# MRCS-Adapter-RJ11.net
KiCad netlist of a schematic drawn in EAGLE
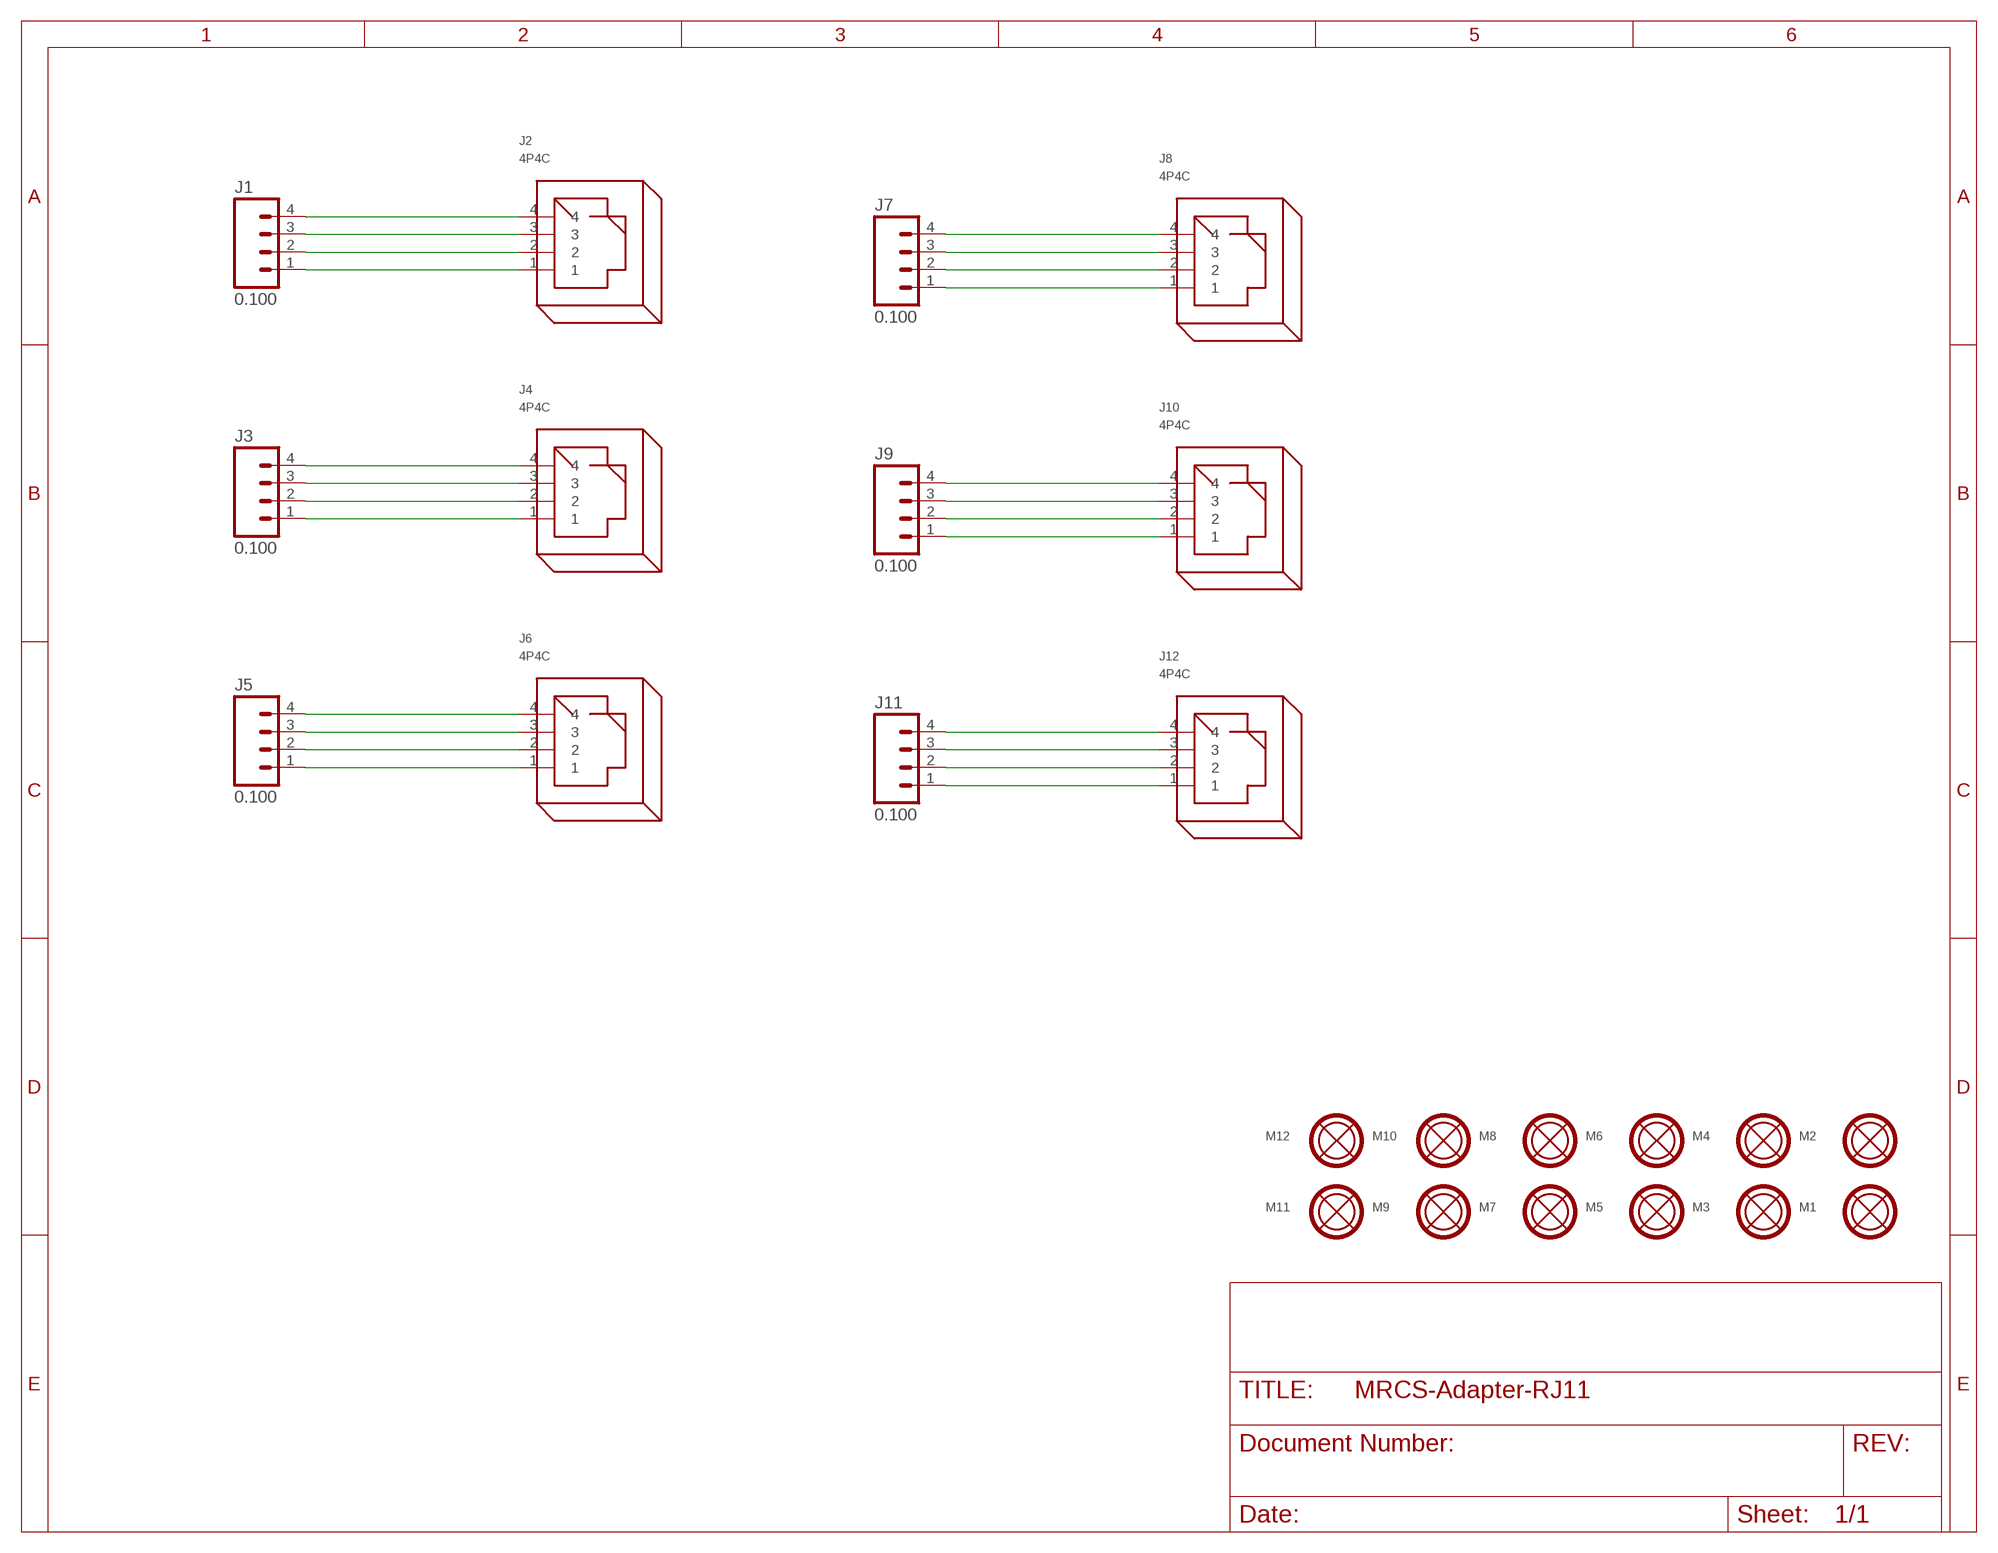
[diagram p0: schematic, sheet 1]

(export (version "E")
  (design (tool "Eeschema 10.0.6"))
  (components
    (comp (ref "J1")
      (value "0.100")
      (footprint "eagle-import:1X04_LOCK")
      (libsource (lib "eagle-import") (part "CONNECTOR-M04LOCK"))
    )
    (comp (ref "J2")
      (value "4P4C")
      (footprint "eagle-import:RJ11")
      (libsource (lib "eagle-import") (part "RJ11"))
    )
    (comp (ref "J3")
      (value "0.100")
      (footprint "eagle-import:1X04_LOCK")
      (libsource (lib "eagle-import") (part "CONNECTOR-M04LOCK"))
    )
    (comp (ref "J4")
      (value "4P4C")
      (footprint "eagle-import:RJ11")
      (libsource (lib "eagle-import") (part "RJ11"))
    )
    (comp (ref "J5")
      (value "0.100")
      (footprint "eagle-import:1X04_LOCK")
      (libsource (lib "eagle-import") (part "CONNECTOR-M04LOCK"))
    )
    (comp (ref "J6")
      (value "4P4C")
      (footprint "eagle-import:RJ11")
      (libsource (lib "eagle-import") (part "RJ11"))
    )
    (comp (ref "J7")
      (value "0.100")
      (footprint "eagle-import:1X04_LOCK")
      (libsource (lib "eagle-import") (part "CONNECTOR-M04LOCK"))
    )
    (comp (ref "J8")
      (value "4P4C")
      (footprint "eagle-import:RJ11")
      (libsource (lib "eagle-import") (part "RJ11"))
    )
    (comp (ref "J9")
      (value "0.100")
      (footprint "eagle-import:1X04_LOCK")
      (libsource (lib "eagle-import") (part "CONNECTOR-M04LOCK"))
    )
    (comp (ref "J10")
      (value "4P4C")
      (footprint "eagle-import:RJ11")
      (libsource (lib "eagle-import") (part "RJ11"))
    )
    (comp (ref "J11")
      (value "0.100")
      (footprint "eagle-import:1X04_LOCK")
      (libsource (lib "eagle-import") (part "CONNECTOR-M04LOCK"))
    )
    (comp (ref "J12")
      (value "4P4C")
      (footprint "eagle-import:RJ11")
      (libsource (lib "eagle-import") (part "RJ11"))
    )
    (comp (ref "M1")
      (value "MOUNTINGHOLE")
      (footprint "eagle-import:MOUNTINGHOLE")
      (libsource (lib "eagle-import") (part "MOUNTINGHOLE"))
    )
    (comp (ref "M2")
      (value "MOUNTINGHOLE")
      (footprint "eagle-import:MOUNTINGHOLE")
      (libsource (lib "eagle-import") (part "MOUNTINGHOLE"))
    )
    (comp (ref "M3")
      (value "MOUNTINGHOLE")
      (footprint "eagle-import:MOUNTINGHOLE")
      (libsource (lib "eagle-import") (part "MOUNTINGHOLE"))
    )
    (comp (ref "M4")
      (value "MOUNTINGHOLE")
      (footprint "eagle-import:MOUNTINGHOLE")
      (libsource (lib "eagle-import") (part "MOUNTINGHOLE"))
    )
    (comp (ref "M5")
      (value "MOUNTINGHOLE")
      (footprint "eagle-import:MOUNTINGHOLE")
      (libsource (lib "eagle-import") (part "MOUNTINGHOLE"))
    )
    (comp (ref "M6")
      (value "MOUNTINGHOLE")
      (footprint "eagle-import:MOUNTINGHOLE")
      (libsource (lib "eagle-import") (part "MOUNTINGHOLE"))
    )
    (comp (ref "M7")
      (value "MOUNTINGHOLE")
      (footprint "eagle-import:MOUNTINGHOLE")
      (libsource (lib "eagle-import") (part "MOUNTINGHOLE"))
    )
    (comp (ref "M8")
      (value "MOUNTINGHOLE")
      (footprint "eagle-import:MOUNTINGHOLE")
      (libsource (lib "eagle-import") (part "MOUNTINGHOLE"))
    )
    (comp (ref "M9")
      (value "MOUNTINGHOLE")
      (footprint "eagle-import:MOUNTINGHOLE")
      (libsource (lib "eagle-import") (part "MOUNTINGHOLE"))
    )
    (comp (ref "M10")
      (value "MOUNTINGHOLE")
      (footprint "eagle-import:MOUNTINGHOLE")
      (libsource (lib "eagle-import") (part "MOUNTINGHOLE"))
    )
    (comp (ref "M11")
      (value "MOUNTINGHOLE")
      (footprint "eagle-import:MOUNTINGHOLE")
      (libsource (lib "eagle-import") (part "MOUNTINGHOLE"))
    )
    (comp (ref "M12")
      (value "MOUNTINGHOLE")
      (footprint "eagle-import:MOUNTINGHOLE")
      (libsource (lib "eagle-import") (part "MOUNTINGHOLE"))
    )
  )
  (nets
    (net (code "1") (name "Net-(J1-Pad1)") (class "Default")
      (node (ref "J1") (pin "1") (pinfunction "1_1") (pintype "passive"))
      (node (ref "J2") (pin "1") (pinfunction "1_1") (pintype "bidirectional"))
    )
    (net (code "2") (name "Net-(J1-Pad2)") (class "Default")
      (node (ref "J1") (pin "2") (pinfunction "2_2") (pintype "passive"))
      (node (ref "J2") (pin "2") (pinfunction "2_2") (pintype "bidirectional"))
    )
    (net (code "3") (name "Net-(J1-Pad3)") (class "Default")
      (node (ref "J1") (pin "3") (pinfunction "3_3") (pintype "passive"))
      (node (ref "J2") (pin "3") (pinfunction "3_3") (pintype "bidirectional"))
    )
    (net (code "4") (name "Net-(J1-Pad4)") (class "Default")
      (node (ref "J1") (pin "4") (pinfunction "4_4") (pintype "passive"))
      (node (ref "J2") (pin "4") (pinfunction "4_4") (pintype "bidirectional"))
    )
    (net (code "5") (name "Net-(J3-Pad1)") (class "Default")
      (node (ref "J3") (pin "1") (pinfunction "1_1") (pintype "passive"))
      (node (ref "J4") (pin "1") (pinfunction "1_1") (pintype "bidirectional"))
    )
    (net (code "6") (name "Net-(J3-Pad2)") (class "Default")
      (node (ref "J3") (pin "2") (pinfunction "2_2") (pintype "passive"))
      (node (ref "J4") (pin "2") (pinfunction "2_2") (pintype "bidirectional"))
    )
    (net (code "7") (name "Net-(J3-Pad3)") (class "Default")
      (node (ref "J3") (pin "3") (pinfunction "3_3") (pintype "passive"))
      (node (ref "J4") (pin "3") (pinfunction "3_3") (pintype "bidirectional"))
    )
    (net (code "8") (name "Net-(J3-Pad4)") (class "Default")
      (node (ref "J3") (pin "4") (pinfunction "4_4") (pintype "passive"))
      (node (ref "J4") (pin "4") (pinfunction "4_4") (pintype "bidirectional"))
    )
    (net (code "9") (name "Net-(J5-Pad1)") (class "Default")
      (node (ref "J5") (pin "1") (pinfunction "1_1") (pintype "passive"))
      (node (ref "J6") (pin "1") (pinfunction "1_1") (pintype "bidirectional"))
    )
    (net (code "10") (name "Net-(J5-Pad2)") (class "Default")
      (node (ref "J5") (pin "2") (pinfunction "2_2") (pintype "passive"))
      (node (ref "J6") (pin "2") (pinfunction "2_2") (pintype "bidirectional"))
    )
    (net (code "11") (name "Net-(J5-Pad3)") (class "Default")
      (node (ref "J5") (pin "3") (pinfunction "3_3") (pintype "passive"))
      (node (ref "J6") (pin "3") (pinfunction "3_3") (pintype "bidirectional"))
    )
    (net (code "12") (name "Net-(J5-Pad4)") (class "Default")
      (node (ref "J5") (pin "4") (pinfunction "4_4") (pintype "passive"))
      (node (ref "J6") (pin "4") (pinfunction "4_4") (pintype "bidirectional"))
    )
    (net (code "13") (name "Net-(J7-Pad1)") (class "Default")
      (node (ref "J7") (pin "1") (pinfunction "1_1") (pintype "passive"))
      (node (ref "J8") (pin "1") (pinfunction "1_1") (pintype "bidirectional"))
    )
    (net (code "14") (name "Net-(J7-Pad2)") (class "Default")
      (node (ref "J7") (pin "2") (pinfunction "2_2") (pintype "passive"))
      (node (ref "J8") (pin "2") (pinfunction "2_2") (pintype "bidirectional"))
    )
    (net (code "15") (name "Net-(J7-Pad3)") (class "Default")
      (node (ref "J7") (pin "3") (pinfunction "3_3") (pintype "passive"))
      (node (ref "J8") (pin "3") (pinfunction "3_3") (pintype "bidirectional"))
    )
    (net (code "16") (name "Net-(J7-Pad4)") (class "Default")
      (node (ref "J7") (pin "4") (pinfunction "4_4") (pintype "passive"))
      (node (ref "J8") (pin "4") (pinfunction "4_4") (pintype "bidirectional"))
    )
    (net (code "17") (name "Net-(J10-Pad1)") (class "Default")
      (node (ref "J10") (pin "1") (pinfunction "1_1") (pintype "bidirectional"))
      (node (ref "J9") (pin "1") (pinfunction "1_1") (pintype "passive"))
    )
    (net (code "18") (name "Net-(J10-Pad2)") (class "Default")
      (node (ref "J10") (pin "2") (pinfunction "2_2") (pintype "bidirectional"))
      (node (ref "J9") (pin "2") (pinfunction "2_2") (pintype "passive"))
    )
    (net (code "19") (name "Net-(J10-Pad3)") (class "Default")
      (node (ref "J10") (pin "3") (pinfunction "3_3") (pintype "bidirectional"))
      (node (ref "J9") (pin "3") (pinfunction "3_3") (pintype "passive"))
    )
    (net (code "20") (name "Net-(J10-Pad4)") (class "Default")
      (node (ref "J10") (pin "4") (pinfunction "4_4") (pintype "bidirectional"))
      (node (ref "J9") (pin "4") (pinfunction "4_4") (pintype "passive"))
    )
    (net (code "21") (name "Net-(J11-Pad1)") (class "Default")
      (node (ref "J11") (pin "1") (pinfunction "1_1") (pintype "passive"))
      (node (ref "J12") (pin "1") (pinfunction "1_1") (pintype "bidirectional"))
    )
    (net (code "22") (name "Net-(J11-Pad2)") (class "Default")
      (node (ref "J11") (pin "2") (pinfunction "2_2") (pintype "passive"))
      (node (ref "J12") (pin "2") (pinfunction "2_2") (pintype "bidirectional"))
    )
    (net (code "23") (name "Net-(J11-Pad3)") (class "Default")
      (node (ref "J11") (pin "3") (pinfunction "3_3") (pintype "passive"))
      (node (ref "J12") (pin "3") (pinfunction "3_3") (pintype "bidirectional"))
    )
    (net (code "24") (name "Net-(J11-Pad4)") (class "Default")
      (node (ref "J11") (pin "4") (pinfunction "4_4") (pintype "passive"))
      (node (ref "J12") (pin "4") (pinfunction "4_4") (pintype "bidirectional"))
    )
  )
)
